# My_Own_Arduino.net
KiCad netlist of a schematic drawn in EasyEDA
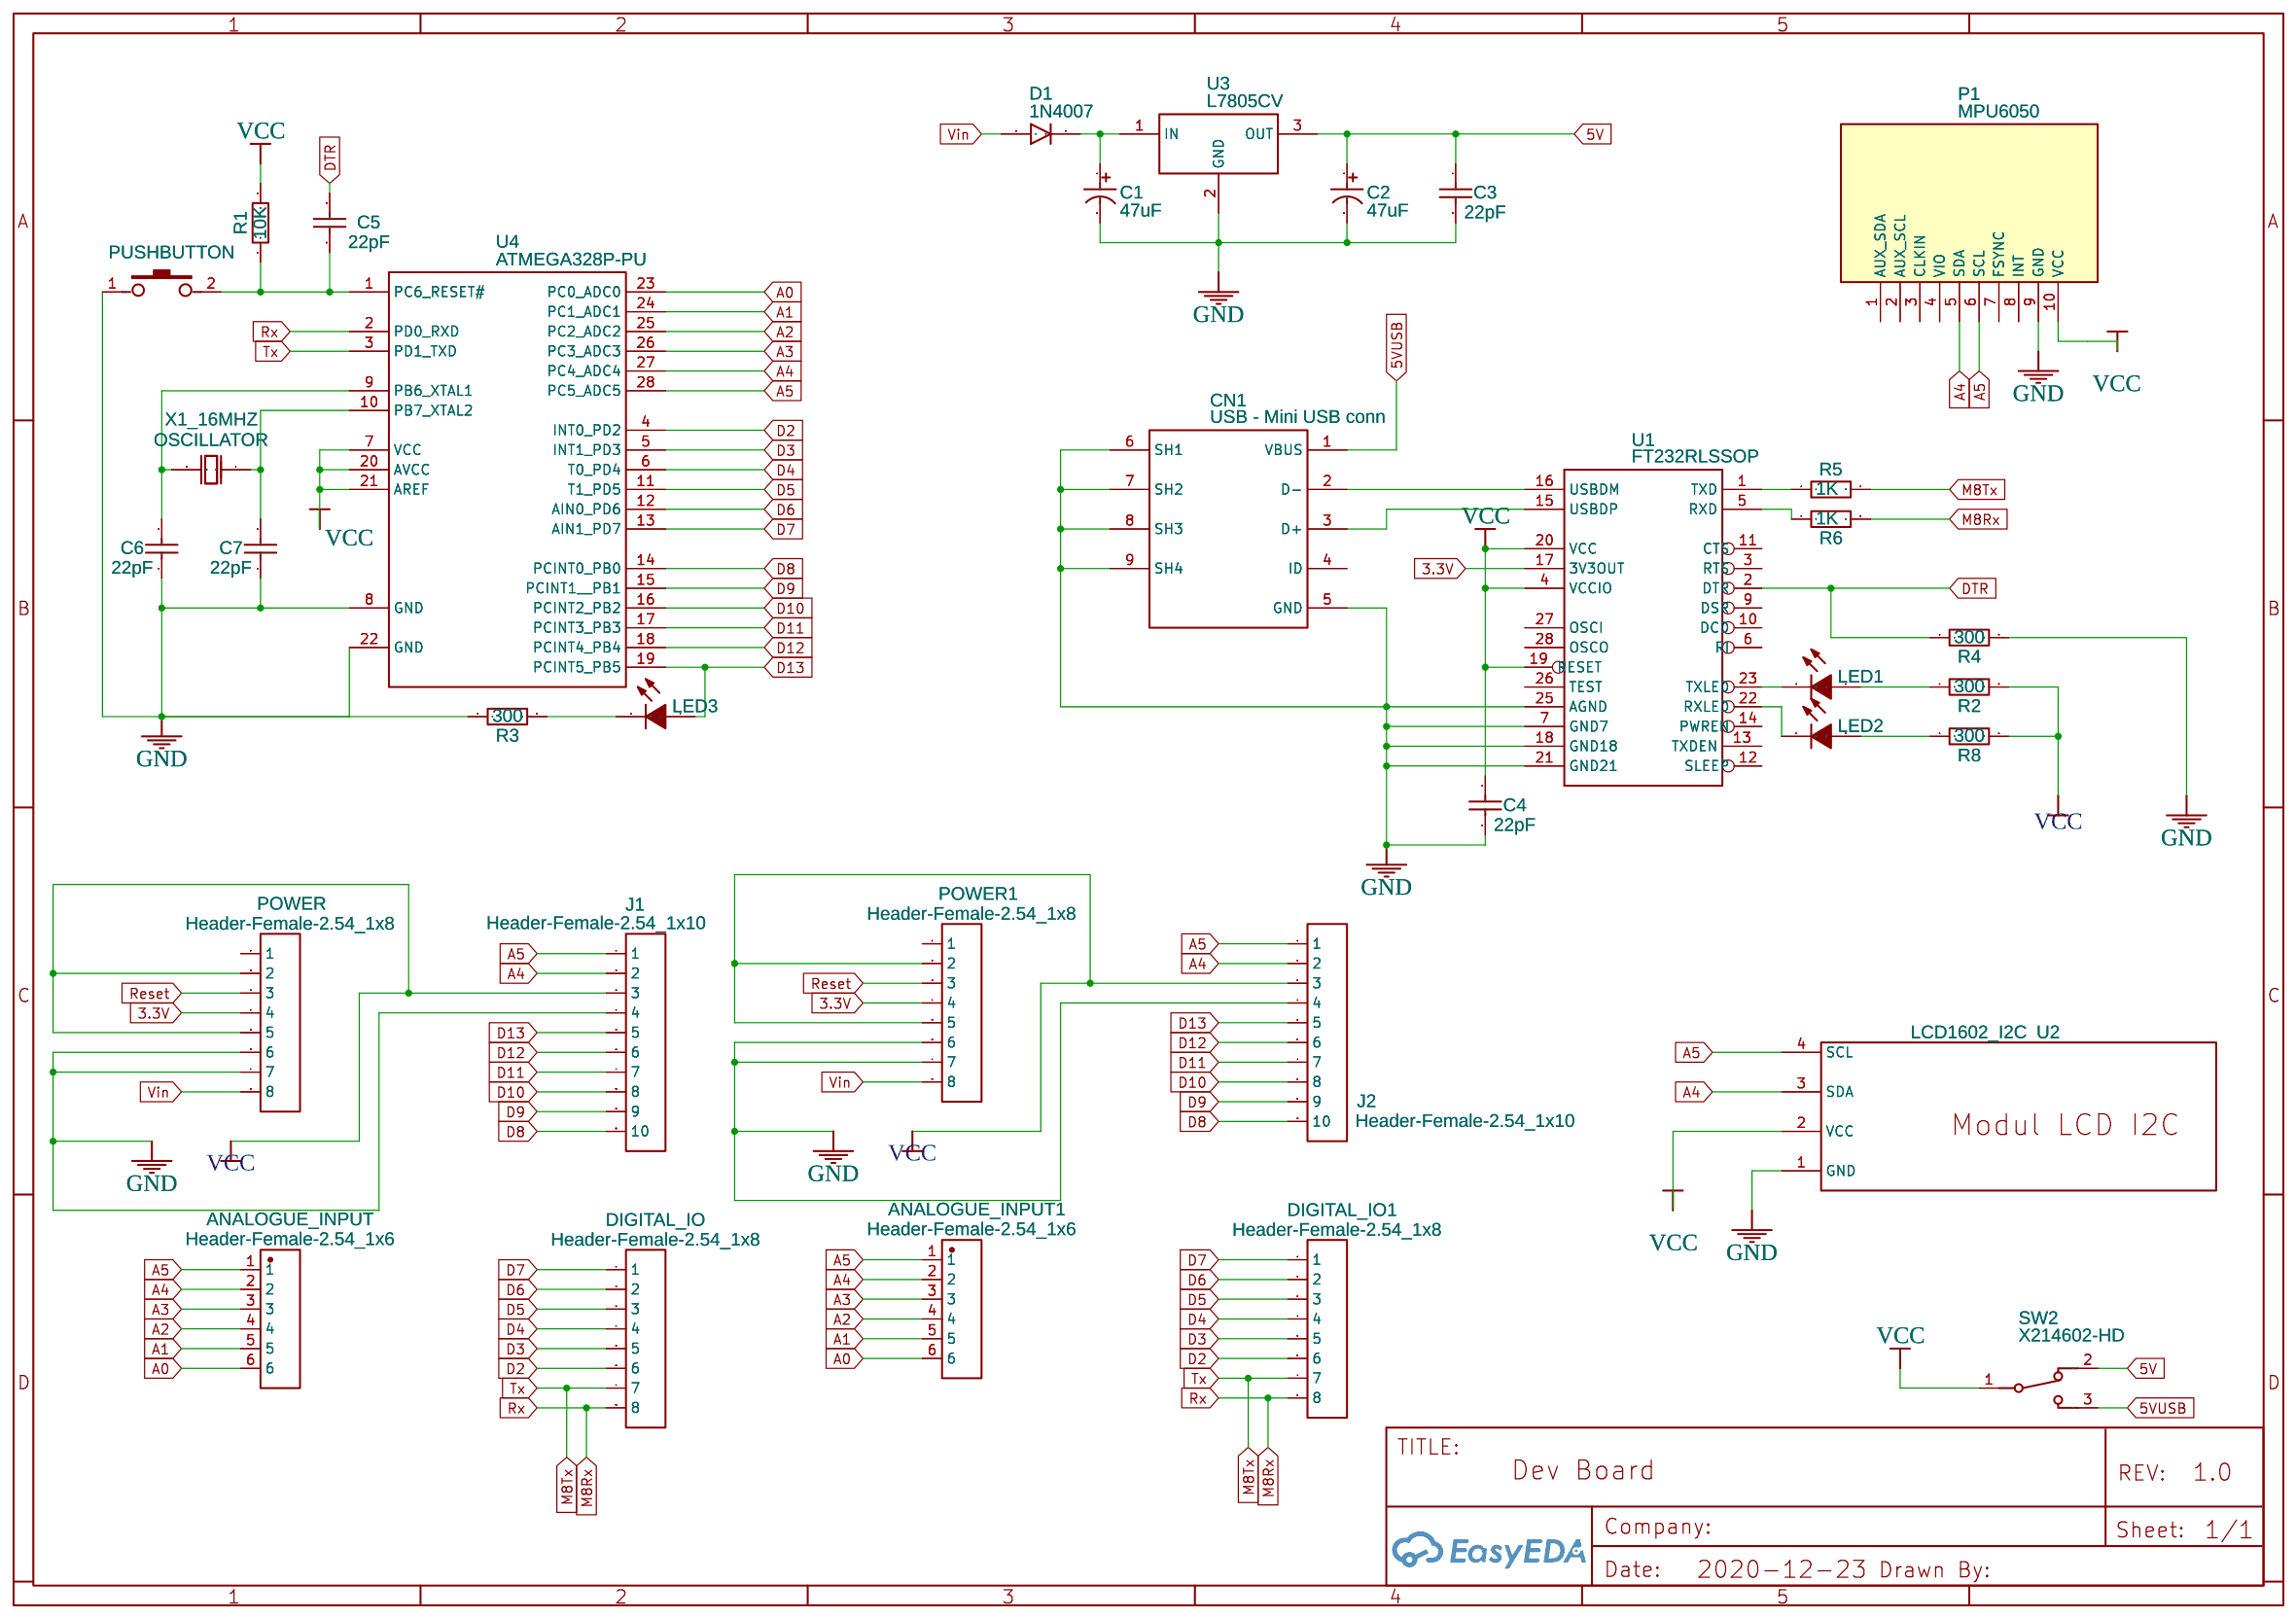
[diagram p0: schematic sheet]

(export (version "E")
  (design (tool "Eeschema 10.0.6"))
  (components
    (comp (ref "ANALOGUE_INPUT")
      (value "Header-Female-2.54_1x6")
      (fields
        (field (name "BOM_Manufacturer Part") "Female header 1*6p")
        (field (name "BOM_Supplier Part") "C40877")
      )
      (libsource (lib "") (part "Header-Female-2.54_1x6"))
    )
    (comp (ref "ANALOGUE_INPUT1")
      (value "Header-Female-2.54_1x6")
      (fields
        (field (name "BOM_Manufacturer Part") "Female header 1*6p")
        (field (name "BOM_Supplier Part") "C40877")
      )
      (libsource (lib "") (part "Header-Female-2.54_1x6"))
    )
    (comp (ref "C1")
      (value "47uF")
      (fields
        (field (name "BOM_Manufacturer Part") "47uF 100V 8*14Black high frequency")
        (field (name "BOM_Supplier Part") "C47903")
      )
      (libsource (lib "") (part "47uF"))
    )
    (comp (ref "C2")
      (value "47uF")
      (fields
        (field (name "BOM_Manufacturer Part") "47uF 100V 8*14Black high frequency")
        (field (name "BOM_Supplier Part") "C47903")
      )
      (libsource (lib "") (part "47uF"))
    )
    (comp (ref "C3")
      (value "22pF")
      (fields
        (field (name "BOM_Manufacturer Part") "Ceramic capacitors47PF 3KV")
        (field (name "BOM_Supplier Part") "C19375")
      )
      (libsource (lib "") (part "Ceramic capacitors47PF 3KV"))
    )
    (comp (ref "C4")
      (value "22pF")
      (fields
        (field (name "BOM_Manufacturer Part") "Ceramic capacitors47PF 3KV")
        (field (name "BOM_Supplier Part") "C19375")
      )
      (libsource (lib "") (part "Ceramic capacitors47PF 3KV"))
    )
    (comp (ref "C5")
      (value "22pF")
      (fields
        (field (name "BOM_Manufacturer Part") "Ceramic capacitors47PF 3KV")
        (field (name "BOM_Supplier Part") "C19375")
      )
      (libsource (lib "") (part "Ceramic capacitors47PF 3KV"))
    )
    (comp (ref "C6")
      (value "22pF")
      (fields
        (field (name "BOM_Manufacturer Part") "Ceramic capacitors47PF 3KV")
        (field (name "BOM_Supplier Part") "C19375")
      )
      (libsource (lib "") (part "Ceramic capacitors47PF 3KV"))
    )
    (comp (ref "C7")
      (value "22pF")
      (fields
        (field (name "BOM_Manufacturer Part") "Ceramic capacitors47PF 3KV")
        (field (name "BOM_Supplier Part") "C19375")
      )
      (libsource (lib "") (part "Ceramic capacitors47PF 3KV"))
    )
    (comp (ref "CN1")
      (value "USB - Mini USB conn")
      (fields (field (name "BOM_Manufacturer Part") "USB - Mini USB"))
      (libsource (lib "") (part "USB - Mini USB conn"))
    )
    (comp (ref "D1")
      (value "1N4007")
      (fields (field (name "BOM_Supplier Part") "C84641"))
      (libsource (lib "") (part "1N4007"))
    )
    (comp (ref "DIGITAL_IO")
      (value "Header-Female-2.54_1x8")
      (fields
        (field (name "BOM_Manufacturer Part") "Female headerHDR1X8-2.54")
        (field (name "BOM_Supplier Part") "C27438")
      )
      (libsource (lib "") (part "Header-Female-2.54_1x8_1"))
    )
    (comp (ref "DIGITAL_IO1")
      (value "Header-Female-2.54_1x8")
      (fields
        (field (name "BOM_Manufacturer Part") "Female headerHDR1X8-2.54")
        (field (name "BOM_Supplier Part") "C27438")
      )
      (libsource (lib "") (part "Header-Female-2.54_1x8_1"))
    )
    (comp (ref "J1")
      (value "Header-Female-2.54_1x10")
      (fields
        (field (name "BOM_Manufacturer Part") "2.54mm 1*10P Straight Female header Gold-plated")
        (field (name "BOM_Supplier Part") "C35445")
      )
      (libsource (lib "") (part "Header-Female-2.54_1x10"))
    )
    (comp (ref "J2")
      (value "Header-Female-2.54_1x10")
      (fields
        (field (name "BOM_Manufacturer Part") "2.54mm 1*10P Straight Female header Gold-plated")
        (field (name "BOM_Supplier Part") "C35445")
      )
      (libsource (lib "") (part "Header-Female-2.54_1x10"))
    )
    (comp (ref "LED1")
      (value "XL-1.8SYT4AD")
      (fields (field (name "BOM_Supplier Part") "undefined"))
      (libsource (lib "") (part "XL-1.8SYT4AD"))
    )
    (comp (ref "LED2")
      (value "XL-1.8SYT4AD")
      (fields (field (name "BOM_Supplier Part") "undefined"))
      (libsource (lib "") (part "XL-1.8SYT4AD"))
    )
    (comp (ref "LED3")
      (value "XL-1.8SYT4AD")
      (fields (field (name "BOM_Supplier Part") "undefined"))
      (libsource (lib "") (part "XL-1.8SYT4AD"))
    )
    (comp (ref "P1") (value "MPU6050") (libsource (lib "") (part "MPU6050")))
    (comp (ref "POWER")
      (value "Header-Female-2.54_1x8")
      (fields
        (field (name "BOM_Manufacturer Part") "Female headerHDR1X8-2.54")
        (field (name "BOM_Supplier Part") "C27438")
      )
      (libsource (lib "") (part "Header-Female-2.54_1x8"))
    )
    (comp (ref "POWER1")
      (value "Header-Female-2.54_1x8")
      (fields
        (field (name "BOM_Manufacturer Part") "Female headerHDR1X8-2.54")
        (field (name "BOM_Supplier Part") "C27438")
      )
      (libsource (lib "") (part "Header-Female-2.54_1x8"))
    )
    (comp (ref "PUSHBUTTON")
      (value "3X4MM TACT")
      (fields (field (name "BOM_Manufacturer Part") "Switch3x4x2"))
      (libsource (lib "") (part "3X4MM TACT"))
    )
    (comp (ref "R1")
      (value "10K")
      (fields
        (field (name "BOM_Manufacturer Part") "MFR-12JT-52-10K")
        (field (name "BOM_Supplier Part") "C176374")
      )
      (libsource (lib "") (part "MFR-12JT-52-10K"))
    )
    (comp (ref "R2")
      (value "300")
      (fields
        (field (name "BOM_Manufacturer Part") "MFR0W4F3000A50")
        (field (name "BOM_Supplier Part") "C58609")
      )
      (libsource (lib "") (part "MFR0W4F3000A50"))
    )
    (comp (ref "R3")
      (value "300")
      (fields
        (field (name "BOM_Manufacturer Part") "MFR0W4F3000A50")
        (field (name "BOM_Supplier Part") "C58609")
      )
      (libsource (lib "") (part "MFR0W4F3000A50"))
    )
    (comp (ref "R4")
      (value "300")
      (fields
        (field (name "BOM_Manufacturer Part") "MFR0W4F3000A50")
        (field (name "BOM_Supplier Part") "C58609")
      )
      (libsource (lib "") (part "MFR0W4F3000A50"))
    )
    (comp (ref "R5")
      (value "1K")
      (fields
        (field (name "BOM_Manufacturer Part") "MFR0W4F3000A50")
        (field (name "BOM_Supplier Part") "C58609")
      )
      (libsource (lib "") (part "MFR0W4F3000A50"))
    )
    (comp (ref "R6")
      (value "1K")
      (fields
        (field (name "BOM_Manufacturer Part") "MFR0W4F3000A50")
        (field (name "BOM_Supplier Part") "C58609")
      )
      (libsource (lib "") (part "MFR0W4F3000A50"))
    )
    (comp (ref "R8")
      (value "300")
      (fields
        (field (name "BOM_Manufacturer Part") "MFR0W4F3000A50")
        (field (name "BOM_Supplier Part") "C58609")
      )
      (libsource (lib "") (part "MFR0W4F3000A50"))
    )
    (comp (ref "SW2")
      (value "X214602-HD")
      (fields (field (name "BOM_Supplier Part") "C712702"))
      (libsource (lib "") (part "X214602-HD"))
    )
    (comp (ref "U1") (value "FT232RLSSOP") (libsource (lib "") (part "FT232RLSSOP")))
    (comp (ref "U2")
      (value "LCD1602_I2C")
      (fields (field (name "BOM_Manufacturer Part") "LCD1602 i2c"))
      (libsource (lib "") (part "LCD1602_I2C"))
    )
    (comp (ref "U3")
      (value "L7805CV")
      (fields (field (name "BOM_Supplier Part") "C111887"))
      (libsource (lib "") (part "L7805CV"))
    )
    (comp (ref "U4")
      (value "ATMEGA328P-PU")
      (fields (field (name "BOM_Supplier Part") "C33901"))
      (libsource (lib "") (part "ATMEGA328P-PU"))
    )
    (comp (ref "X1_16MHZ") (value "OSCILLATOR") (libsource (lib "") (part "OSCILLATOR")))
  )
  (nets
    (net (code "1") (name "3.3V") (class "Default")
      (node (ref "POWER") (pin "4") (pinfunction "4_4") (pintype "input"))
      (node (ref "POWER1") (pin "4") (pinfunction "4_4") (pintype "input"))
      (node (ref "U1") (pin "17") (pinfunction "3V3OUT_17") (pintype "output"))
    )
    (net (code "2") (name "5V") (class "Default")
      (node (ref "C2") (pin "1") (pinfunction "1_1") (pintype "input"))
      (node (ref "C3") (pin "1") (pinfunction "1_1") (pintype "input"))
      (node (ref "SW2") (pin "2") (pinfunction "2_2") (pintype "unspecified"))
      (node (ref "U3") (pin "3") (pinfunction "OUT_3") (pintype "passive"))
    )
    (net (code "3") (name "5VUSB") (class "Default")
      (node (ref "CN1") (pin "1") (pinfunction "VBUS_1") (pintype "passive"))
      (node (ref "SW2") (pin "3") (pinfunction "3_3") (pintype "unspecified"))
    )
    (net (code "4") (name "A0") (class "Default")
      (node (ref "ANALOGUE_INPUT") (pin "6") (pinfunction "6_6") (pintype "unspecified"))
      (node (ref "ANALOGUE_INPUT1") (pin "6") (pinfunction "6_6") (pintype "unspecified"))
      (node (ref "U4") (pin "23") (pinfunction "PC0_ADC0_23") (pintype "bidirectional"))
    )
    (net (code "5") (name "A1") (class "Default")
      (node (ref "ANALOGUE_INPUT") (pin "5") (pinfunction "5_5") (pintype "unspecified"))
      (node (ref "ANALOGUE_INPUT1") (pin "5") (pinfunction "5_5") (pintype "unspecified"))
      (node (ref "U4") (pin "24") (pinfunction "PC1_ADC1_24") (pintype "bidirectional"))
    )
    (net (code "6") (name "A2") (class "Default")
      (node (ref "ANALOGUE_INPUT") (pin "4") (pinfunction "4_4") (pintype "unspecified"))
      (node (ref "ANALOGUE_INPUT1") (pin "4") (pinfunction "4_4") (pintype "unspecified"))
      (node (ref "U4") (pin "25") (pinfunction "PC2_ADC2_25") (pintype "bidirectional"))
    )
    (net (code "7") (name "A3") (class "Default")
      (node (ref "ANALOGUE_INPUT") (pin "3") (pinfunction "3_3") (pintype "unspecified"))
      (node (ref "ANALOGUE_INPUT1") (pin "3") (pinfunction "3_3") (pintype "unspecified"))
      (node (ref "U4") (pin "26") (pinfunction "PC3_ADC3_26") (pintype "bidirectional"))
    )
    (net (code "8") (name "A4") (class "Default")
      (node (ref "ANALOGUE_INPUT") (pin "2") (pinfunction "2_2") (pintype "unspecified"))
      (node (ref "ANALOGUE_INPUT1") (pin "2") (pinfunction "2_2") (pintype "unspecified"))
      (node (ref "J1") (pin "2") (pinfunction "2_2") (pintype "input"))
      (node (ref "J2") (pin "2") (pinfunction "2_2") (pintype "input"))
      (node (ref "P1") (pin "5") (pinfunction "SDA_5") (pintype "unspecified"))
      (node (ref "U2") (pin "3") (pinfunction "SDA_3") (pintype "unspecified"))
      (node (ref "U4") (pin "27") (pinfunction "PC4_ADC4_27") (pintype "bidirectional"))
    )
    (net (code "9") (name "A5") (class "Default")
      (node (ref "ANALOGUE_INPUT") (pin "1") (pinfunction "1_1") (pintype "unspecified"))
      (node (ref "ANALOGUE_INPUT1") (pin "1") (pinfunction "1_1") (pintype "unspecified"))
      (node (ref "J1") (pin "1") (pinfunction "1_1") (pintype "input"))
      (node (ref "J2") (pin "1") (pinfunction "1_1") (pintype "input"))
      (node (ref "P1") (pin "6") (pinfunction "SCL_6") (pintype "unspecified"))
      (node (ref "U2") (pin "4") (pinfunction "SCL_4") (pintype "unspecified"))
      (node (ref "U4") (pin "28") (pinfunction "PC5_ADC5_28") (pintype "bidirectional"))
    )
    (net (code "10") (name "D2") (class "Default")
      (node (ref "DIGITAL_IO") (pin "6") (pinfunction "6_6") (pintype "input"))
      (node (ref "DIGITAL_IO1") (pin "6") (pinfunction "6_6") (pintype "input"))
      (node (ref "U4") (pin "4") (pinfunction "INT0_PD2_4") (pintype "bidirectional"))
    )
    (net (code "11") (name "D3") (class "Default")
      (node (ref "DIGITAL_IO") (pin "5") (pinfunction "5_5") (pintype "input"))
      (node (ref "DIGITAL_IO1") (pin "5") (pinfunction "5_5") (pintype "input"))
      (node (ref "U4") (pin "5") (pinfunction "INT1_PD3_5") (pintype "bidirectional"))
    )
    (net (code "12") (name "D4") (class "Default")
      (node (ref "DIGITAL_IO") (pin "4") (pinfunction "4_4") (pintype "input"))
      (node (ref "DIGITAL_IO1") (pin "4") (pinfunction "4_4") (pintype "input"))
      (node (ref "U4") (pin "6") (pinfunction "T0_PD4_6") (pintype "bidirectional"))
    )
    (net (code "13") (name "D5") (class "Default")
      (node (ref "DIGITAL_IO") (pin "3") (pinfunction "3_3") (pintype "input"))
      (node (ref "DIGITAL_IO1") (pin "3") (pinfunction "3_3") (pintype "input"))
      (node (ref "U4") (pin "11") (pinfunction "T1_PD5_11") (pintype "bidirectional"))
    )
    (net (code "14") (name "D6") (class "Default")
      (node (ref "DIGITAL_IO") (pin "2") (pinfunction "2_2") (pintype "input"))
      (node (ref "DIGITAL_IO1") (pin "2") (pinfunction "2_2") (pintype "input"))
      (node (ref "U4") (pin "12") (pinfunction "AIN0_PD6_12") (pintype "bidirectional"))
    )
    (net (code "15") (name "D7") (class "Default")
      (node (ref "DIGITAL_IO") (pin "1") (pinfunction "1_1") (pintype "input"))
      (node (ref "DIGITAL_IO1") (pin "1") (pinfunction "1_1") (pintype "input"))
      (node (ref "U4") (pin "13") (pinfunction "AIN1_PD7_13") (pintype "bidirectional"))
    )
    (net (code "16") (name "D8") (class "Default")
      (node (ref "J1") (pin "10") (pinfunction "10_10") (pintype "input"))
      (node (ref "J2") (pin "10") (pinfunction "10_10") (pintype "input"))
      (node (ref "U4") (pin "14") (pinfunction "PCINT0_PB0_14") (pintype "bidirectional"))
    )
    (net (code "17") (name "D9") (class "Default")
      (node (ref "J1") (pin "9") (pinfunction "9_9") (pintype "input"))
      (node (ref "J2") (pin "9") (pinfunction "9_9") (pintype "input"))
      (node (ref "U4") (pin "15") (pinfunction "PCINT1__PB1_15") (pintype "bidirectional"))
    )
    (net (code "18") (name "D10") (class "Default")
      (node (ref "J1") (pin "8") (pinfunction "8_8") (pintype "input"))
      (node (ref "J2") (pin "8") (pinfunction "8_8") (pintype "input"))
      (node (ref "U4") (pin "16") (pinfunction "PCINT2_PB2_16") (pintype "bidirectional"))
    )
    (net (code "19") (name "D11") (class "Default")
      (node (ref "J1") (pin "7") (pinfunction "7_7") (pintype "input"))
      (node (ref "J2") (pin "7") (pinfunction "7_7") (pintype "input"))
      (node (ref "U4") (pin "17") (pinfunction "PCINT3_PB3_17") (pintype "bidirectional"))
    )
    (net (code "20") (name "D12") (class "Default")
      (node (ref "J1") (pin "6") (pinfunction "6_6") (pintype "input"))
      (node (ref "J2") (pin "6") (pinfunction "6_6") (pintype "input"))
      (node (ref "U4") (pin "18") (pinfunction "PCINT4_PB4_18") (pintype "bidirectional"))
    )
    (net (code "21") (name "D13") (class "Default")
      (node (ref "J1") (pin "5") (pinfunction "5_5") (pintype "input"))
      (node (ref "J2") (pin "5") (pinfunction "5_5") (pintype "input"))
      (node (ref "LED3") (pin "1") (pinfunction "A_1") (pintype "input"))
      (node (ref "U4") (pin "19") (pinfunction "PCINT5_PB5_19") (pintype "bidirectional"))
    )
    (net (code "22") (name "DTR") (class "Default")
      (node (ref "C5") (pin "1") (pinfunction "1_1") (pintype "input"))
      (node (ref "R4") (pin "1") (pinfunction "1_1") (pintype "input"))
      (node (ref "U1") (pin "2") (pinfunction "DTR_2") (pintype "output"))
    )
    (net (code "23") (name "GND") (class "Default")
      (node (ref "C1") (pin "2") (pinfunction "2_2") (pintype "input"))
      (node (ref "C2") (pin "2") (pinfunction "2_2") (pintype "input"))
      (node (ref "C3") (pin "2") (pinfunction "2_2") (pintype "input"))
      (node (ref "C4") (pin "2") (pinfunction "2_2") (pintype "input"))
      (node (ref "C6") (pin "2") (pinfunction "2_2") (pintype "input"))
      (node (ref "C7") (pin "2") (pinfunction "2_2") (pintype "input"))
      (node (ref "CN1") (pin "5") (pinfunction "GND_5") (pintype "passive"))
      (node (ref "CN1") (pin "6") (pinfunction "SH1_6") (pintype "passive"))
      (node (ref "CN1") (pin "7") (pinfunction "SH2_7") (pintype "passive"))
      (node (ref "CN1") (pin "8") (pinfunction "SH3_8") (pintype "passive"))
      (node (ref "CN1") (pin "9") (pinfunction "SH4_9") (pintype "passive"))
      (node (ref "J1") (pin "4") (pinfunction "4_4") (pintype "input"))
      (node (ref "J2") (pin "4") (pinfunction "4_4") (pintype "input"))
      (node (ref "P1") (pin "9") (pinfunction "GND_9") (pintype "unspecified"))
      (node (ref "POWER") (pin "6") (pinfunction "6_6") (pintype "input"))
      (node (ref "POWER") (pin "7") (pinfunction "7_7") (pintype "input"))
      (node (ref "POWER1") (pin "6") (pinfunction "6_6") (pintype "input"))
      (node (ref "POWER1") (pin "7") (pinfunction "7_7") (pintype "input"))
      (node (ref "PUSHBUTTON") (pin "1") (pinfunction "1_1") (pintype "input"))
      (node (ref "R3") (pin "1") (pinfunction "1_1") (pintype "input"))
      (node (ref "R4") (pin "2") (pinfunction "2_2") (pintype "input"))
      (node (ref "U1") (pin "18") (pinfunction "GND18_18") (pintype "passive"))
      (node (ref "U1") (pin "21") (pinfunction "GND21_21") (pintype "passive"))
      (node (ref "U1") (pin "25") (pinfunction "AGND_25") (pintype "passive"))
      (node (ref "U1") (pin "7") (pinfunction "GND7_7") (pintype "passive"))
      (node (ref "U2") (pin "1") (pinfunction "GND_1") (pintype "unspecified"))
      (node (ref "U3") (pin "2") (pinfunction "GND_2") (pintype "passive"))
      (node (ref "U4") (pin "22") (pinfunction "GND_22") (pintype "passive"))
      (node (ref "U4") (pin "8") (pinfunction "GND_8") (pintype "passive"))
    )
    (net (code "24") (name "M8Rx") (class "Default")
      (node (ref "DIGITAL_IO") (pin "8") (pinfunction "8_8") (pintype "input"))
      (node (ref "DIGITAL_IO1") (pin "8") (pinfunction "8_8") (pintype "input"))
      (node (ref "R6") (pin "2") (pinfunction "2_2") (pintype "input"))
      (node (ref "U4") (pin "2") (pinfunction "PD0_RXD_2") (pintype "bidirectional"))
    )
    (net (code "25") (name "M8Tx") (class "Default")
      (node (ref "DIGITAL_IO") (pin "7") (pinfunction "7_7") (pintype "input"))
      (node (ref "DIGITAL_IO1") (pin "7") (pinfunction "7_7") (pintype "input"))
      (node (ref "R5") (pin "2") (pinfunction "2_2") (pintype "input"))
      (node (ref "U4") (pin "3") (pinfunction "PD1_TXD_3") (pintype "bidirectional"))
    )
    (net (code "26") (name "Net-(CN1-D+)") (class "Default")
      (node (ref "CN1") (pin "3") (pinfunction "D+_3") (pintype "bidirectional"))
      (node (ref "U1") (pin "15") (pinfunction "USBDP_15") (pintype "unspecified"))
    )
    (net (code "27") (name "Net-(CN1-D-)") (class "Default")
      (node (ref "CN1") (pin "2") (pinfunction "D-_2") (pintype "bidirectional"))
      (node (ref "U1") (pin "16") (pinfunction "USBDM_16") (pintype "unspecified"))
    )
    (net (code "28") (name "Net-(D1-C)") (class "Default")
      (node (ref "C1") (pin "1") (pinfunction "1_1") (pintype "input"))
      (node (ref "D1") (pin "2") (pinfunction "C_2") (pintype "unspecified"))
      (node (ref "U3") (pin "1") (pinfunction "IN_1") (pintype "passive"))
    )
    (net (code "29") (name "Net-(LED1-A)") (class "Default")
      (node (ref "LED1") (pin "1") (pinfunction "A_1") (pintype "input"))
      (node (ref "R2") (pin "1") (pinfunction "1_1") (pintype "input"))
    )
    (net (code "30") (name "Net-(LED1-C)") (class "Default")
      (node (ref "LED1") (pin "2") (pinfunction "C_2") (pintype "input"))
      (node (ref "U1") (pin "23") (pinfunction "TXLED_23") (pintype "input"))
    )
    (net (code "31") (name "Net-(LED2-A)") (class "Default")
      (node (ref "LED2") (pin "1") (pinfunction "A_1") (pintype "input"))
      (node (ref "R8") (pin "1") (pinfunction "1_1") (pintype "input"))
    )
    (net (code "32") (name "Net-(LED2-C)") (class "Default")
      (node (ref "LED2") (pin "2") (pinfunction "C_2") (pintype "input"))
      (node (ref "U1") (pin "22") (pinfunction "RXLED_22") (pintype "input"))
    )
    (net (code "33") (name "Net-(LED3-C)") (class "Default")
      (node (ref "LED3") (pin "2") (pinfunction "C_2") (pintype "input"))
      (node (ref "R3") (pin "2") (pinfunction "2_2") (pintype "input"))
    )
    (net (code "34") (name "Net-(U1-RXD)") (class "Default")
      (node (ref "R6") (pin "1") (pinfunction "1_1") (pintype "input"))
      (node (ref "U1") (pin "5") (pinfunction "RXD_5") (pintype "input"))
    )
    (net (code "35") (name "Net-(U1-TXD)") (class "Default")
      (node (ref "R5") (pin "1") (pinfunction "1_1") (pintype "input"))
      (node (ref "U1") (pin "1") (pinfunction "TXD_1") (pintype "output"))
    )
    (net (code "36") (name "Net-(U4-PB6_XTAL1)") (class "Default")
      (node (ref "C6") (pin "1") (pinfunction "1_1") (pintype "input"))
      (node (ref "U4") (pin "9") (pinfunction "PB6_XTAL1_9") (pintype "bidirectional"))
      (node (ref "X1_16MHZ") (pin "2") (pinfunction "OSC2_2") (pintype "input"))
    )
    (net (code "37") (name "Net-(U4-PB7_XTAL2)") (class "Default")
      (node (ref "C7") (pin "1") (pinfunction "1_1") (pintype "input"))
      (node (ref "U4") (pin "10") (pinfunction "PB7_XTAL2_10") (pintype "bidirectional"))
      (node (ref "X1_16MHZ") (pin "1") (pinfunction "OSC1_1") (pintype "input"))
    )
    (net (code "38") (name "Net-(U4-PC6_RESET#)") (class "Default")
      (node (ref "C5") (pin "2") (pinfunction "2_2") (pintype "input"))
      (node (ref "PUSHBUTTON") (pin "2") (pinfunction "2_2") (pintype "input"))
      (node (ref "R1") (pin "2") (pinfunction "2_2") (pintype "unspecified"))
      (node (ref "U4") (pin "1") (pinfunction "PC6_RESET#_1") (pintype "bidirectional"))
    )
    (net (code "39") (name "Reset") (class "Default")
      (node (ref "POWER") (pin "3") (pinfunction "3_3") (pintype "input"))
      (node (ref "POWER1") (pin "3") (pinfunction "3_3") (pintype "input"))
    )
    (net (code "40") (name "VCC") (class "Default")
      (node (ref "C4") (pin "1") (pinfunction "1_1") (pintype "input"))
      (node (ref "J1") (pin "3") (pinfunction "3_3") (pintype "input"))
      (node (ref "J2") (pin "3") (pinfunction "3_3") (pintype "input"))
      (node (ref "P1") (pin "10") (pinfunction "VCC_10") (pintype "unspecified"))
      (node (ref "POWER") (pin "2") (pinfunction "2_2") (pintype "input"))
      (node (ref "POWER") (pin "5") (pinfunction "5_5") (pintype "input"))
      (node (ref "POWER1") (pin "2") (pinfunction "2_2") (pintype "input"))
      (node (ref "POWER1") (pin "5") (pinfunction "5_5") (pintype "input"))
      (node (ref "R1") (pin "1") (pinfunction "1_1") (pintype "unspecified"))
      (node (ref "R2") (pin "2") (pinfunction "2_2") (pintype "input"))
      (node (ref "R8") (pin "2") (pinfunction "2_2") (pintype "input"))
      (node (ref "SW2") (pin "1") (pinfunction "1_1") (pintype "unspecified"))
      (node (ref "U1") (pin "19") (pinfunction "RESET_19") (pintype "input"))
      (node (ref "U1") (pin "20") (pinfunction "VCC_20") (pintype "passive"))
      (node (ref "U1") (pin "4") (pinfunction "VCCIO_4") (pintype "passive"))
      (node (ref "U2") (pin "2") (pinfunction "VCC_2") (pintype "unspecified"))
      (node (ref "U4") (pin "20") (pinfunction "AVCC_20") (pintype "passive"))
      (node (ref "U4") (pin "21") (pinfunction "AREF_21") (pintype "passive"))
      (node (ref "U4") (pin "7") (pinfunction "VCC_7") (pintype "passive"))
    )
    (net (code "41") (name "Vin") (class "Default")
      (node (ref "D1") (pin "1") (pinfunction "A_1") (pintype "unspecified"))
      (node (ref "POWER") (pin "8") (pinfunction "8_8") (pintype "input"))
      (node (ref "POWER1") (pin "8") (pinfunction "8_8") (pintype "input"))
    )
    (net (code "42") (name "unconnected-(CN1-ID-Pad4)") (class "Default")
      (node (ref "CN1") (pin "4") (pinfunction "ID_4") (pintype "bidirectional"))
    )
    (net (code "43") (name "unconnected-(P1-AUX_SCL-Pad2)") (class "Default")
      (node (ref "P1") (pin "2") (pinfunction "AUX_SCL_2") (pintype "unspecified"))
    )
    (net (code "44") (name "unconnected-(P1-AUX_SDA-Pad1)") (class "Default")
      (node (ref "P1") (pin "1") (pinfunction "AUX_SDA_1") (pintype "unspecified"))
    )
    (net (code "45") (name "unconnected-(P1-CLKIN-Pad3)") (class "Default")
      (node (ref "P1") (pin "3") (pinfunction "CLKIN_3") (pintype "unspecified"))
    )
    (net (code "46") (name "unconnected-(P1-FSYNC-Pad7)") (class "Default")
      (node (ref "P1") (pin "7") (pinfunction "FSYNC_7") (pintype "unspecified"))
    )
    (net (code "47") (name "unconnected-(P1-INT-Pad8)") (class "Default")
      (node (ref "P1") (pin "8") (pinfunction "INT_8") (pintype "unspecified"))
    )
    (net (code "48") (name "unconnected-(P1-VIO-Pad4)") (class "Default")
      (node (ref "P1") (pin "4") (pinfunction "VIO_4") (pintype "unspecified"))
    )
    (net (code "49") (name "unconnected-(POWER-Pad1)") (class "Default")
      (node (ref "POWER") (pin "1") (pinfunction "1_1") (pintype "input"))
    )
    (net (code "50") (name "unconnected-(POWER1-Pad1)") (class "Default")
      (node (ref "POWER1") (pin "1") (pinfunction "1_1") (pintype "input"))
    )
    (net (code "51") (name "unconnected-(U1-CTS-Pad11)") (class "Default")
      (node (ref "U1") (pin "11") (pinfunction "CTS_11") (pintype "input"))
    )
    (net (code "52") (name "unconnected-(U1-DCD-Pad10)") (class "Default")
      (node (ref "U1") (pin "10") (pinfunction "DCD_10") (pintype "input"))
    )
    (net (code "53") (name "unconnected-(U1-DSR-Pad9)") (class "Default")
      (node (ref "U1") (pin "9") (pinfunction "DSR_9") (pintype "input"))
    )
    (net (code "54") (name "unconnected-(U1-OSCI-Pad27)") (class "Default")
      (node (ref "U1") (pin "27") (pinfunction "OSCI_27") (pintype "input"))
    )
    (net (code "55") (name "unconnected-(U1-OSCO-Pad28)") (class "Default")
      (node (ref "U1") (pin "28") (pinfunction "OSCO_28") (pintype "output"))
    )
    (net (code "56") (name "unconnected-(U1-PWREN-Pad14)") (class "Default")
      (node (ref "U1") (pin "14") (pinfunction "PWREN_14") (pintype "input"))
    )
    (net (code "57") (name "unconnected-(U1-RI-Pad6)") (class "Default")
      (node (ref "U1") (pin "6") (pinfunction "RI_6") (pintype "input"))
    )
    (net (code "58") (name "unconnected-(U1-RTS-Pad3)") (class "Default")
      (node (ref "U1") (pin "3") (pinfunction "RTS_3") (pintype "output"))
    )
    (net (code "59") (name "unconnected-(U1-SLEEP-Pad12)") (class "Default")
      (node (ref "U1") (pin "12") (pinfunction "SLEEP_12") (pintype "input"))
    )
    (net (code "60") (name "unconnected-(U1-TEST-Pad26)") (class "Default")
      (node (ref "U1") (pin "26") (pinfunction "TEST_26") (pintype "input"))
    )
    (net (code "61") (name "unconnected-(U1-TXDEN-Pad13)") (class "Default")
      (node (ref "U1") (pin "13") (pinfunction "TXDEN_13") (pintype "input"))
    )
  )
)
